# Power_supply_MAX6350CSA.net
KiCad netlist of a schematic drawn in Altium Designer
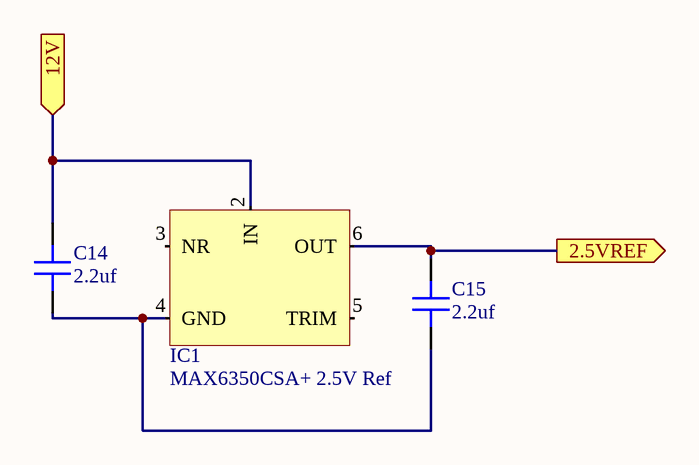
[diagram p0: Power_supply_MAX6350CSA.SchDoc]

(export (version "E")
  (design (tool "Eeschema 10.0.6"))
  (components
    (comp (ref "C14")
      (value "2.2uf")
      (footprint "CAP 0603/1608")
      (fields
        (field (name "Comment") "Capacitor MLCC 2.2uf 16V CAP 0603/1608")
        (field (name "CREATED_BY") "Nick Mah")
      )
      (libsource (lib "Altium-Lib") (part "Capacitor"))
    )
    (comp (ref "C15")
      (value "2.2uf")
      (footprint "CAP 0603/1608")
      (fields
        (field (name "Comment") "Capacitor MLCC 2.2uf 16V CAP 0603/1608")
        (field (name "CREATED_BY") "Nick Mah")
      )
      (libsource (lib "Altium-Lib") (part "Capacitor"))
    )
    (comp (ref "IC1")
      (value "MAX6350CSA+ 2.5V Ref")
      (footprint "SOIC-8")
      (description "IC VREF SERIES 5V 8SOIC")
      (libsource (lib "Altium-Lib") (part "MAX6350CSA+ 2.5V Ref"))
    )
  )
  (nets
    (net (code "1") (name "/2.5VREF") (class "Default")
      (node (ref "C15") (pin "2") (pinfunction "2_2") (pintype "passive"))
      (node (ref "IC1") (pin "6") (pinfunction "OUT_6") (pintype "input"))
    )
    (net (code "2") (name "/12V") (class "Default")
      (node (ref "C14") (pin "2") (pinfunction "2_2") (pintype "passive"))
      (node (ref "IC1") (pin "2") (pinfunction "IN_2") (pintype "input"))
    )
    (net (code "3") (name "Net-(IC1-GND)") (class "Default")
      (node (ref "C14") (pin "1") (pinfunction "1_1") (pintype "passive"))
      (node (ref "C15") (pin "1") (pinfunction "1_1") (pintype "passive"))
      (node (ref "IC1") (pin "4") (pinfunction "GND_4") (pintype "input"))
    )
    (net (code "4") (name "unconnected-(IC1-NR-Pad3)") (class "Default")
      (node (ref "IC1") (pin "3") (pinfunction "NR_3") (pintype "input"))
    )
    (net (code "5") (name "unconnected-(IC1-TRIM-Pad5)") (class "Default")
      (node (ref "IC1") (pin "5") (pinfunction "TRIM_5") (pintype "input"))
    )
  )
)
